# RTC_DS1307.net
KiCad netlist of a schematic drawn in Altium Designer
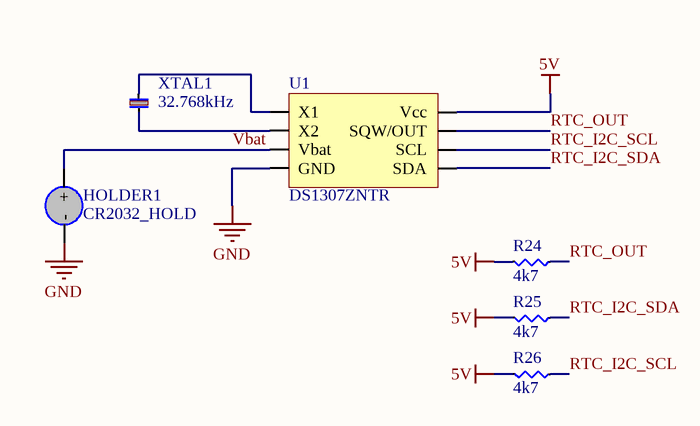
[diagram p0: RTC_DS1307.SchDoc]

(export (version "E")
  (design (tool "Eeschema 10.0.6"))
  (components
    (comp (ref "HOLDER1")
      (value "CR2032_HOLD")
      (footprint "BATTERYHOLDER_2032")
      (description "BATTERY HOLDER COIN 20MM PC PIN")
      (fields
        (field (name "MANUFACTURER") "Memory Protection Devices")
        (field (name "MANUFACTURER PART NUMBER") "BS-7")
      )
      (libsource (lib "SEMATIK_LIB") (part "BS-7"))
    )
    (comp (ref "R24")
      (value "4k7")
      (footprint "R_0805")
      (description "RES SMD 4.7K OHM 5% 1/8W 0805")
      (fields
        (field (name "MANUFACTURER") "Yageo")
        (field (name "MANUFACTURER PART NUMBER") "RC0805JR-074K7L")
      )
      (libsource (lib "SEMATIK_LIB") (part "RC0805JR-074K7L"))
    )
    (comp (ref "R25")
      (value "4k7")
      (footprint "R_0805")
      (description "RES SMD 4.7K OHM 5% 1/8W 0805")
      (fields
        (field (name "MANUFACTURER") "Yageo")
        (field (name "MANUFACTURER PART NUMBER") "RC0805JR-074K7L")
      )
      (libsource (lib "SEMATIK_LIB") (part "RC0805JR-074K7L"))
    )
    (comp (ref "R26")
      (value "4k7")
      (footprint "R_0805")
      (description "RES SMD 4.7K OHM 5% 1/8W 0805")
      (fields
        (field (name "MANUFACTURER") "Yageo")
        (field (name "MANUFACTURER PART NUMBER") "RC0805JR-074K7L")
      )
      (libsource (lib "SEMATIK_LIB") (part "RC0805JR-074K7L"))
    )
    (comp (ref "U1")
      (value "DS1307ZNTR")
      (footprint "SOP8")
      (description "IC RTC CLK/CALENDAR I2C 8-SOIC")
      (fields (field (name "MANUFACTURER") "Maxim") (field (name "VOLTAGE") "7V"))
      (libsource (lib "SEMATIK_LIB") (part "DS1307ZNTR"))
    )
    (comp (ref "XTAL1")
      (value "32.768kHz")
      (footprint "CRYSTAL_CYLINDER")
      (description "CRYSTAL 32.7680KHZ 12.5PF T/H")
      (fields
        (field (name "MANUFACTURER") "ECS International")
        (field (name "MANUFACTURER PART NUMBER") "ECS-3X8X")
      )
      (libsource (lib "SEMATIK_LIB") (part "ECS-3X8X"))
    )
  )
  (nets
    (net (code "1") (name "/RTC_I2C_SCL") (class "Default")
      (node (ref "R26") (pin "1") (pinfunction "1_1") (pintype "passive"))
      (node (ref "U1") (pin "6") (pinfunction "SCL_6") (pintype "passive"))
    )
    (net (code "2") (name "/RTC_I2C_SDA") (class "Default")
      (node (ref "R25") (pin "1") (pinfunction "1_1") (pintype "passive"))
      (node (ref "U1") (pin "5") (pinfunction "SDA_5") (pintype "passive"))
    )
    (net (code "3") (name "/RTC_OUT") (class "Default")
      (node (ref "R24") (pin "1") (pinfunction "1_1") (pintype "passive"))
      (node (ref "U1") (pin "7") (pinfunction "SQW/OUT_7") (pintype "passive"))
    )
    (net (code "4") (name "/Vbat") (class "Default")
      (node (ref "HOLDER1") (pin "1") (pinfunction "+_1") (pintype "passive"))
      (node (ref "U1") (pin "3") (pinfunction "Vbat_3") (pintype "passive"))
    )
    (net (code "5") (name "5V") (class "Default")
      (node (ref "R24") (pin "2") (pinfunction "2_2") (pintype "passive"))
      (node (ref "R25") (pin "2") (pinfunction "2_2") (pintype "passive"))
      (node (ref "R26") (pin "2") (pinfunction "2_2") (pintype "passive"))
      (node (ref "U1") (pin "8") (pinfunction "Vcc_8") (pintype "passive"))
    )
    (net (code "6") (name "GND") (class "Default")
      (node (ref "HOLDER1") (pin "2") (pinfunction "-_2") (pintype "passive"))
      (node (ref "U1") (pin "4") (pinfunction "GND_4") (pintype "passive"))
    )
    (net (code "7") (name "Net-(U1-X1)") (class "Default")
      (node (ref "U1") (pin "1") (pinfunction "X1_1") (pintype "passive"))
      (node (ref "XTAL1") (pin "2") (pinfunction "2_2") (pintype "passive"))
    )
    (net (code "8") (name "Net-(U1-X2)") (class "Default")
      (node (ref "U1") (pin "2") (pinfunction "X2_2") (pintype "passive"))
      (node (ref "XTAL1") (pin "1") (pinfunction "1_1") (pintype "passive"))
    )
  )
)
